# master-sim800.net
KiCad netlist of a schematic drawn in EAGLE
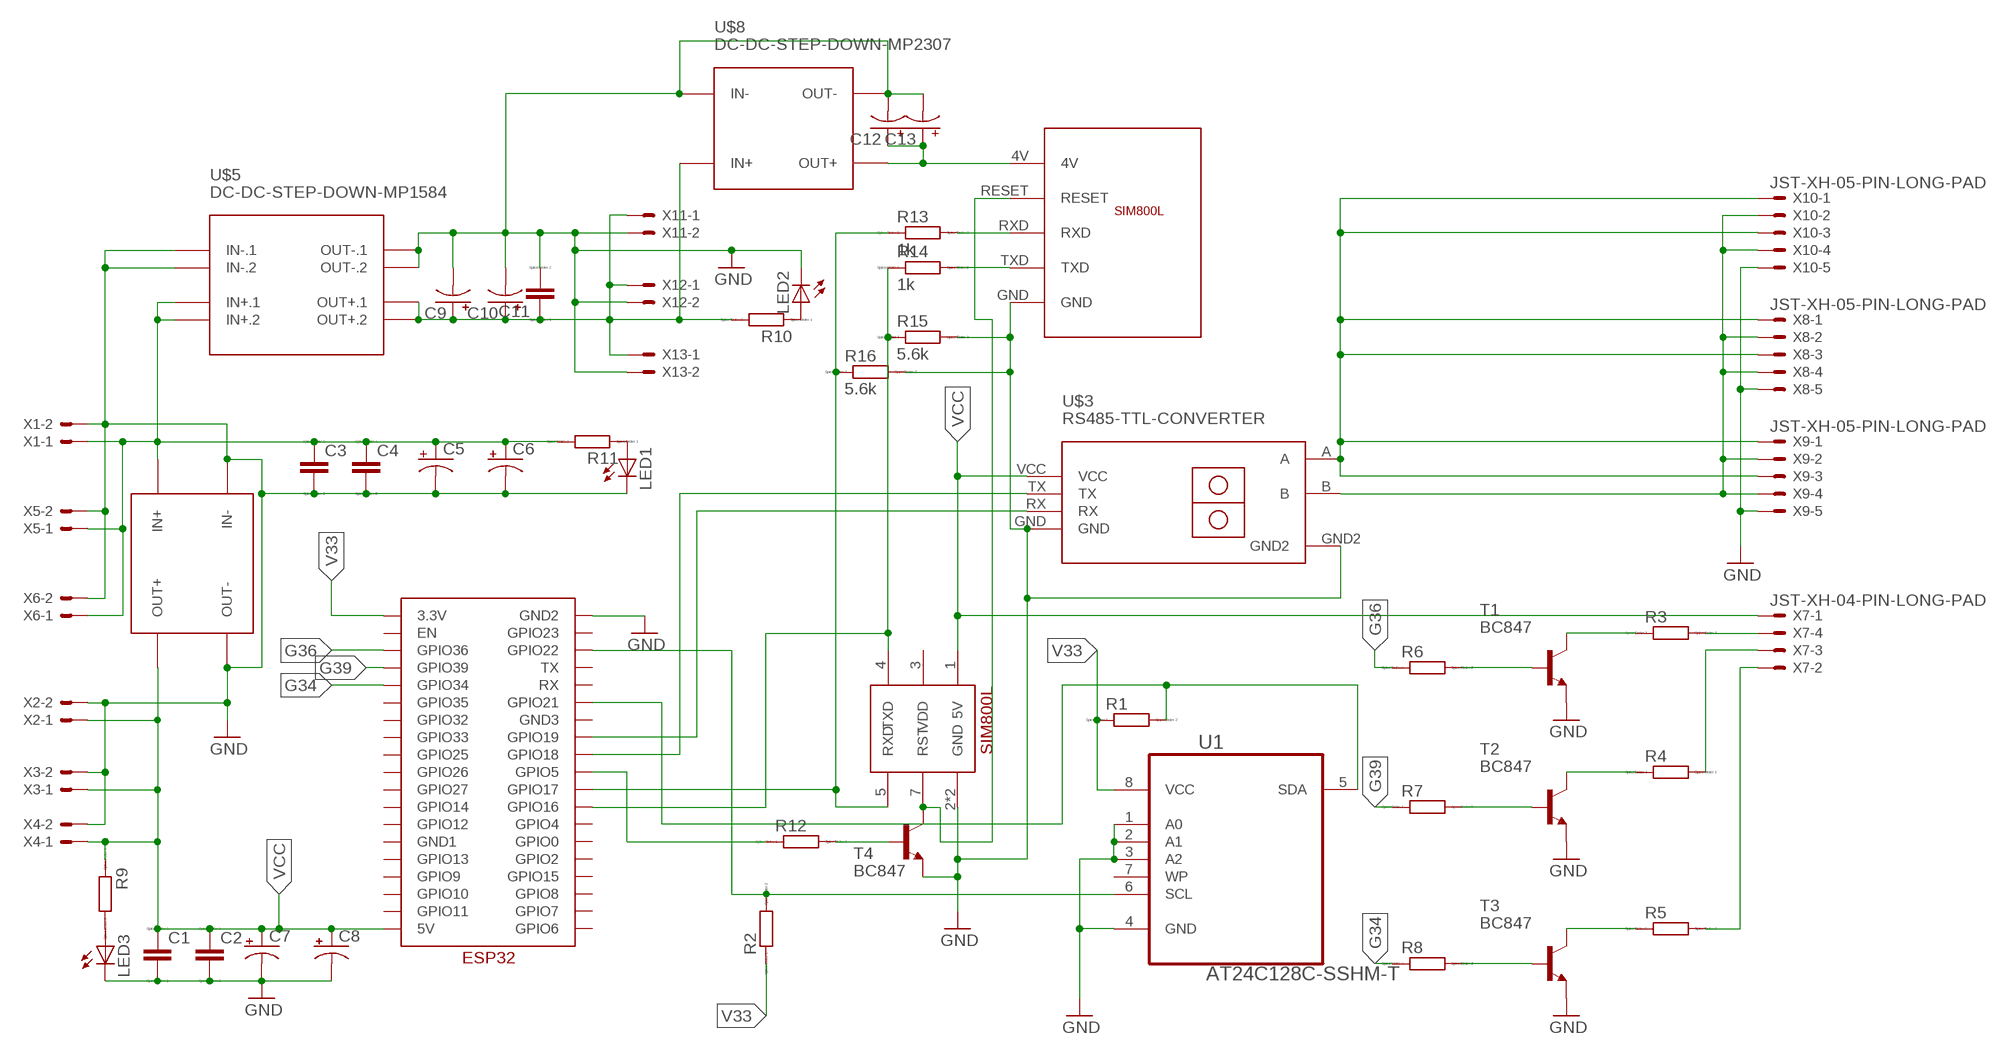
[diagram p0: schematic, sheet 1]

(export (version "E")
  (design (tool "Eeschema 10.0.6"))
  (components
    (comp (ref "C1") (value "C") (footprint "eagle-import:C0805") (libsource (lib "eagle-import") (part "C")))
    (comp (ref "C2") (value "C") (footprint "eagle-import:C0805") (libsource (lib "eagle-import") (part "C")))
    (comp (ref "C3") (value "C") (footprint "eagle-import:C0805") (libsource (lib "eagle-import") (part "C")))
    (comp (ref "C4") (value "C") (footprint "eagle-import:C0805") (libsource (lib "eagle-import") (part "C")))
    (comp (ref "C5")
      (value "CPOL-USE5-8.5")
      (footprint "eagle-import:E5-8,5")
      (libsource (lib "eagle-import") (part "CPOL-USE5-8.5"))
    )
    (comp (ref "C6")
      (value "CPOL-USE5-8.5")
      (footprint "eagle-import:E5-8,5")
      (libsource (lib "eagle-import") (part "CPOL-USE5-8.5"))
    )
    (comp (ref "C7")
      (value "CPOL-USE5-8.5")
      (footprint "eagle-import:E5-8,5")
      (libsource (lib "eagle-import") (part "CPOL-USE5-8.5"))
    )
    (comp (ref "C8")
      (value "CPOL-USE5-8.5")
      (footprint "eagle-import:E5-8,5")
      (libsource (lib "eagle-import") (part "CPOL-USE5-8.5"))
    )
    (comp (ref "C9")
      (value "CPOL-USE5-6")
      (footprint "eagle-import:E5-6")
      (libsource (lib "eagle-import") (part "CPOL-USE5-6"))
    )
    (comp (ref "C10")
      (value "CPOL-USE5-6")
      (footprint "eagle-import:E5-6")
      (libsource (lib "eagle-import") (part "CPOL-USE5-6"))
    )
    (comp (ref "C11")
      (value "C")
      (footprint "eagle-import:C0805")
      (libsource (lib "eagle-import") (part "C"))
    )
    (comp (ref "C12")
      (value "CPOL-USE5-8.5")
      (footprint "eagle-import:E5-8,5")
      (libsource (lib "eagle-import") (part "CPOL-USE5-8.5"))
    )
    (comp (ref "C13")
      (value "CPOL-USE5-8.5")
      (footprint "eagle-import:E5-8,5")
      (libsource (lib "eagle-import") (part "CPOL-USE5-8.5"))
    )
    (comp (ref "LED1")
      (value "LEDCHIPLED_1206")
      (footprint "eagle-import:CHIPLED_1206")
      (libsource (lib "eagle-import") (part "LEDCHIPLED_1206"))
    )
    (comp (ref "LED2")
      (value "LEDCHIPLED_1206")
      (footprint "eagle-import:CHIPLED_1206")
      (libsource (lib "eagle-import") (part "LEDCHIPLED_1206"))
    )
    (comp (ref "LED3")
      (value "LEDCHIPLED_1206")
      (footprint "eagle-import:CHIPLED_1206")
      (libsource (lib "eagle-import") (part "LEDCHIPLED_1206"))
    )
    (comp (ref "R1")
      (value "RR1206")
      (footprint "eagle-import:R1206")
      (libsource (lib "eagle-import") (part "RR1206"))
    )
    (comp (ref "R2")
      (value "RR1206")
      (footprint "eagle-import:R1206")
      (libsource (lib "eagle-import") (part "RR1206"))
    )
    (comp (ref "R3")
      (value "RR1206")
      (footprint "eagle-import:R1206")
      (libsource (lib "eagle-import") (part "RR1206"))
    )
    (comp (ref "R4")
      (value "RR1206")
      (footprint "eagle-import:R1206")
      (libsource (lib "eagle-import") (part "RR1206"))
    )
    (comp (ref "R5")
      (value "RR1206")
      (footprint "eagle-import:R1206")
      (libsource (lib "eagle-import") (part "RR1206"))
    )
    (comp (ref "R6")
      (value "RR1206")
      (footprint "eagle-import:R1206")
      (libsource (lib "eagle-import") (part "RR1206"))
    )
    (comp (ref "R7")
      (value "RR1206")
      (footprint "eagle-import:R1206")
      (libsource (lib "eagle-import") (part "RR1206"))
    )
    (comp (ref "R8")
      (value "RR1206")
      (footprint "eagle-import:R1206")
      (libsource (lib "eagle-import") (part "RR1206"))
    )
    (comp (ref "R9")
      (value "RR1206")
      (footprint "eagle-import:R1206")
      (libsource (lib "eagle-import") (part "RR1206"))
    )
    (comp (ref "R10")
      (value "RR1206")
      (footprint "eagle-import:R1206")
      (libsource (lib "eagle-import") (part "RR1206"))
    )
    (comp (ref "R11")
      (value "RR1206")
      (footprint "eagle-import:R1206")
      (libsource (lib "eagle-import") (part "RR1206"))
    )
    (comp (ref "R12")
      (value "RR1206")
      (footprint "eagle-import:R1206")
      (libsource (lib "eagle-import") (part "RR1206"))
    )
    (comp (ref "R13")
      (value "1k")
      (footprint "eagle-import:R1206")
      (libsource (lib "eagle-import") (part "RR1206"))
    )
    (comp (ref "R14")
      (value "1k")
      (footprint "eagle-import:R1206")
      (libsource (lib "eagle-import") (part "RR1206"))
    )
    (comp (ref "R15")
      (value "5.6k")
      (footprint "eagle-import:R1206")
      (libsource (lib "eagle-import") (part "RR1206"))
    )
    (comp (ref "R16")
      (value "5.6k")
      (footprint "eagle-import:R1206")
      (libsource (lib "eagle-import") (part "RR1206"))
    )
    (comp (ref "T1")
      (value "BC847")
      (footprint "eagle-import:SOT23")
      (libsource (lib "eagle-import") (part "BC847"))
    )
    (comp (ref "T2")
      (value "BC847")
      (footprint "eagle-import:SOT23")
      (libsource (lib "eagle-import") (part "BC847"))
    )
    (comp (ref "T3")
      (value "BC847")
      (footprint "eagle-import:SOT23")
      (libsource (lib "eagle-import") (part "BC847"))
    )
    (comp (ref "T4")
      (value "BC847")
      (footprint "eagle-import:SOT23")
      (libsource (lib "eagle-import") (part "BC847"))
    )
    (comp (ref "U$1")
      (value "ESP32")
      (footprint "eagle-import:ESP32")
      (libsource (lib "eagle-import") (part "ESP32"))
    )
    (comp (ref "U$2")
      (value "SIM800L")
      (footprint "eagle-import:SIP")
      (libsource (lib "eagle-import") (part "SIM800L"))
    )
    (comp (ref "U$3")
      (value "RS485-TTL-CONVERTER")
      (footprint "eagle-import:RS485-TTL-CONVERTER")
      (libsource (lib "eagle-import") (part "RS485-TTL-CONVERTER"))
    )
    (comp (ref "U$4")
      (value "DC-DC-STEP-DOWN-MP2307")
      (footprint "eagle-import:DC-DC-STEP-DOWN-MP2307")
      (libsource (lib "eagle-import") (part "DC-DC-STEP-DOWN-MP2307"))
    )
    (comp (ref "U$5")
      (value "DC-DC-STEP-DOWN-MP1584")
      (footprint "eagle-import:DC-DC-STEP-DOWN-MP1584")
      (libsource (lib "eagle-import") (part "DC-DC-STEP-DOWN-MP1584"))
    )
    (comp (ref "U$7")
      (value "SIM800L-V1")
      (footprint "eagle-import:SIM800L")
      (libsource (lib "eagle-import") (part "SIM800L-V1"))
    )
    (comp (ref "U$8")
      (value "DC-DC-STEP-DOWN-MP2307")
      (footprint "eagle-import:DC-DC-STEP-DOWN-MP2307")
      (libsource (lib "eagle-import") (part "DC-DC-STEP-DOWN-MP2307"))
    )
    (comp (ref "U1")
      (value "AT24C128C-SSHM-T")
      (footprint "eagle-import:SOIC127P600X175-8N")
      (fields (field (name "MF") "Microchip"))
      (libsource (lib "eagle-import") (part "AT24C128C-SSHM-T"))
    )
    (comp (ref "X1")
      (value "JST-XH-02-PIN-LONG-PAD")
      (footprint "eagle-import:JST-XH-02-PACKAGE-LONG-PAD")
      (libsource (lib "eagle-import") (part "JST-XH-02-PIN-LONG-PAD"))
    )
    (comp (ref "X2")
      (value "JST-XH-02-PIN-LONG-PAD")
      (footprint "eagle-import:JST-XH-02-PACKAGE-LONG-PAD")
      (libsource (lib "eagle-import") (part "JST-XH-02-PIN-LONG-PAD"))
    )
    (comp (ref "X3")
      (value "JST-XH-02-PIN-LONG-PAD")
      (footprint "eagle-import:JST-XH-02-PACKAGE-LONG-PAD")
      (libsource (lib "eagle-import") (part "JST-XH-02-PIN-LONG-PAD"))
    )
    (comp (ref "X4")
      (value "JST-XH-02-PIN-LONG-PAD")
      (footprint "eagle-import:JST-XH-02-PACKAGE-LONG-PAD")
      (libsource (lib "eagle-import") (part "JST-XH-02-PIN-LONG-PAD"))
    )
    (comp (ref "X5")
      (value "JST-XH-02-PIN-LONG-PAD")
      (footprint "eagle-import:JST-XH-02-PACKAGE-LONG-PAD")
      (libsource (lib "eagle-import") (part "JST-XH-02-PIN-LONG-PAD"))
    )
    (comp (ref "X6")
      (value "JST-XH-02-PIN-LONG-PAD")
      (footprint "eagle-import:JST-XH-02-PACKAGE-LONG-PAD")
      (libsource (lib "eagle-import") (part "JST-XH-02-PIN-LONG-PAD"))
    )
    (comp (ref "X7")
      (value "JST-XH-04-PIN-LONG-PAD")
      (footprint "eagle-import:JST-XH-04-PACKAGE-LONG-PAD")
      (libsource (lib "eagle-import") (part "JST-XH-04-PIN-LONG-PAD"))
    )
    (comp (ref "X8")
      (value "JST-XH-05-PIN-LONG-PAD")
      (footprint "eagle-import:JST-XH-05-PACKAGE-LONG-PAD")
      (libsource (lib "eagle-import") (part "JST-XH-05-PIN-LONG-PAD"))
    )
    (comp (ref "X9")
      (value "JST-XH-05-PIN-LONG-PAD")
      (footprint "eagle-import:JST-XH-05-PACKAGE-LONG-PAD")
      (libsource (lib "eagle-import") (part "JST-XH-05-PIN-LONG-PAD"))
    )
    (comp (ref "X10")
      (value "JST-XH-05-PIN-LONG-PAD")
      (footprint "eagle-import:JST-XH-05-PACKAGE-LONG-PAD")
      (libsource (lib "eagle-import") (part "JST-XH-05-PIN-LONG-PAD"))
    )
    (comp (ref "X11")
      (value "JST-XH-02-PIN-LONG-PAD")
      (footprint "eagle-import:JST-XH-02-PACKAGE-LONG-PAD")
      (libsource (lib "eagle-import") (part "JST-XH-02-PIN-LONG-PAD"))
    )
    (comp (ref "X12")
      (value "JST-XH-02-PIN-LONG-PAD")
      (footprint "eagle-import:JST-XH-02-PACKAGE-LONG-PAD")
      (libsource (lib "eagle-import") (part "JST-XH-02-PIN-LONG-PAD"))
    )
    (comp (ref "X13")
      (value "JST-XH-02-PIN-LONG-PAD")
      (footprint "eagle-import:JST-XH-02-PACKAGE-LONG-PAD")
      (libsource (lib "eagle-import") (part "JST-XH-02-PIN-LONG-PAD"))
    )
  )
  (nets
    (net (code "1") (name "G34") (class "Default")
      (node (ref "R8") (pin "1") (pinfunction "1_1") (pintype "passive"))
      (node (ref "U$1") (pin "GPIO34") (pinfunction "GPIO34_GPIO34") (pintype "bidirectional"))
    )
    (net (code "2") (name "G36") (class "Default")
      (node (ref "R6") (pin "1") (pinfunction "1_1") (pintype "passive"))
      (node (ref "U$1") (pin "GPIO36") (pinfunction "GPIO36_GPIO36") (pintype "bidirectional"))
    )
    (net (code "3") (name "G39") (class "Default")
      (node (ref "R7") (pin "1") (pinfunction "1_1") (pintype "passive"))
      (node (ref "U$1") (pin "GPIO39") (pinfunction "GPIO39_GPIO39") (pintype "bidirectional"))
    )
    (net (code "4") (name "GND") (class "Default")
      (node (ref "C1") (pin "2") (pinfunction "2_2") (pintype "passive"))
      (node (ref "C10") (pin "-") (pinfunction "-_-") (pintype "passive"))
      (node (ref "C11") (pin "2") (pinfunction "2_2") (pintype "passive"))
      (node (ref "C12") (pin "-") (pinfunction "-_-") (pintype "passive"))
      (node (ref "C13") (pin "-") (pinfunction "-_-") (pintype "passive"))
      (node (ref "C2") (pin "2") (pinfunction "2_2") (pintype "passive"))
      (node (ref "C3") (pin "2") (pinfunction "2_2") (pintype "passive"))
      (node (ref "C4") (pin "2") (pinfunction "2_2") (pintype "passive"))
      (node (ref "C5") (pin "-") (pinfunction "-_-") (pintype "passive"))
      (node (ref "C6") (pin "-") (pinfunction "-_-") (pintype "passive"))
      (node (ref "C7") (pin "-") (pinfunction "-_-") (pintype "passive"))
      (node (ref "C8") (pin "-") (pinfunction "-_-") (pintype "passive"))
      (node (ref "C9") (pin "-") (pinfunction "-_-") (pintype "passive"))
      (node (ref "LED1") (pin "C") (pinfunction "C_C") (pintype "passive"))
      (node (ref "LED2") (pin "C") (pinfunction "C_C") (pintype "passive"))
      (node (ref "LED3") (pin "C") (pinfunction "C_C") (pintype "passive"))
      (node (ref "R15") (pin "2") (pinfunction "2_2") (pintype "passive"))
      (node (ref "R16") (pin "2") (pinfunction "2_2") (pintype "passive"))
      (node (ref "T1") (pin "2") (pinfunction "E_2") (pintype "passive"))
      (node (ref "T2") (pin "2") (pinfunction "E_2") (pintype "passive"))
      (node (ref "T3") (pin "2") (pinfunction "E_2") (pintype "passive"))
      (node (ref "T4") (pin "2") (pinfunction "E_2") (pintype "passive"))
      (node (ref "U$1") (pin "GND2") (pinfunction "GND2_GND2") (pintype "bidirectional"))
      (node (ref "U$2") (pin "2") (pinfunction "GND_2") (pintype "bidirectional"))
      (node (ref "U$2") (pin "6") (pinfunction "GND_6") (pintype "bidirectional"))
      (node (ref "U$3") (pin "GND") (pinfunction "GND_GND") (pintype "passive"))
      (node (ref "U$3") (pin "GND2") (pinfunction "GND2_GND2") (pintype "power_in"))
      (node (ref "U$4") (pin "IN-") (pinfunction "IN-_IN-") (pintype "bidirectional"))
      (node (ref "U$4") (pin "OUT-") (pinfunction "OUT-_OUT-") (pintype "bidirectional"))
      (node (ref "U$5") (pin "IN-.1") (pinfunction "IN-.1_IN-.1") (pintype "bidirectional"))
      (node (ref "U$5") (pin "IN-.2") (pinfunction "IN-.2_IN-.2") (pintype "bidirectional"))
      (node (ref "U$5") (pin "OUT-.1") (pinfunction "OUT-.1_OUT-.1") (pintype "bidirectional"))
      (node (ref "U$5") (pin "OUT-.2") (pinfunction "OUT-.2_OUT-.2") (pintype "bidirectional"))
      (node (ref "U$7") (pin "GND") (pinfunction "GND_GND") (pintype "bidirectional"))
      (node (ref "U$8") (pin "IN-") (pinfunction "IN-_IN-") (pintype "bidirectional"))
      (node (ref "U$8") (pin "OUT-") (pinfunction "OUT-_OUT-") (pintype "bidirectional"))
      (node (ref "U1") (pin "1") (pinfunction "A0_1") (pintype "input"))
      (node (ref "U1") (pin "2") (pinfunction "A1_2") (pintype "input"))
      (node (ref "U1") (pin "3") (pinfunction "A2_3") (pintype "input"))
      (node (ref "U1") (pin "4") (pinfunction "GND_4") (pintype "passive"))
      (node (ref "X1") (pin "2") (pinfunction "S_2") (pintype "passive"))
      (node (ref "X10") (pin "5") (pinfunction "S_5") (pintype "passive"))
      (node (ref "X11") (pin "2") (pinfunction "S_2") (pintype "passive"))
      (node (ref "X12") (pin "2") (pinfunction "S_2") (pintype "passive"))
      (node (ref "X13") (pin "2") (pinfunction "S_2") (pintype "passive"))
      (node (ref "X2") (pin "2") (pinfunction "S_2") (pintype "passive"))
      (node (ref "X3") (pin "2") (pinfunction "S_2") (pintype "passive"))
      (node (ref "X4") (pin "2") (pinfunction "S_2") (pintype "passive"))
      (node (ref "X5") (pin "2") (pinfunction "S_2") (pintype "passive"))
      (node (ref "X6") (pin "2") (pinfunction "S_2") (pintype "passive"))
      (node (ref "X8") (pin "5") (pinfunction "S_5") (pintype "passive"))
      (node (ref "X9") (pin "5") (pinfunction "S_5") (pintype "passive"))
    )
    (net (code "5") (name "Net-(C12-Pad+)") (class "Default")
      (node (ref "C12") (pin "+") (pinfunction "+_+") (pintype "passive"))
      (node (ref "C13") (pin "+") (pinfunction "+_+") (pintype "passive"))
      (node (ref "U$7") (pin "4V") (pinfunction "4V_4V") (pintype "bidirectional"))
      (node (ref "U$8") (pin "OUT+") (pinfunction "OUT+_OUT+") (pintype "bidirectional"))
    )
    (net (code "6") (name "Net-(LED1-PadA)") (class "Default")
      (node (ref "LED1") (pin "A") (pinfunction "A_A") (pintype "passive"))
      (node (ref "R11") (pin "1") (pinfunction "1_1") (pintype "passive"))
    )
    (net (code "7") (name "Net-(LED2-PadA)") (class "Default")
      (node (ref "LED2") (pin "A") (pinfunction "A_A") (pintype "passive"))
      (node (ref "R10") (pin "1") (pinfunction "1_1") (pintype "passive"))
    )
    (net (code "8") (name "Net-(LED3-PadA)") (class "Default")
      (node (ref "LED3") (pin "A") (pinfunction "A_A") (pintype "passive"))
      (node (ref "R9") (pin "2") (pinfunction "2_2") (pintype "passive"))
    )
    (net (code "9") (name "Net-(R12-Pad1)") (class "Default")
      (node (ref "R12") (pin "1") (pinfunction "1_1") (pintype "passive"))
      (node (ref "U$1") (pin "GPIO5") (pinfunction "GPIO5_GPIO5") (pintype "bidirectional"))
    )
    (net (code "10") (name "Net-(R13-Pad2)") (class "Default")
      (node (ref "R13") (pin "2") (pinfunction "2_2") (pintype "passive"))
      (node (ref "U$7") (pin "RXD") (pinfunction "RXD_RXD") (pintype "bidirectional"))
    )
    (net (code "11") (name "Net-(R14-Pad2)") (class "Default")
      (node (ref "R14") (pin "2") (pinfunction "2_2") (pintype "passive"))
      (node (ref "U$7") (pin "TXD") (pinfunction "TXD_TXD") (pintype "bidirectional"))
    )
    (net (code "12") (name "Net-(T1-B)") (class "Default")
      (node (ref "R6") (pin "2") (pinfunction "2_2") (pintype "passive"))
      (node (ref "T1") (pin "1") (pinfunction "B_1") (pintype "passive"))
    )
    (net (code "13") (name "Net-(T1-C)") (class "Default")
      (node (ref "R3") (pin "1") (pinfunction "1_1") (pintype "passive"))
      (node (ref "T1") (pin "3") (pinfunction "C_3") (pintype "passive"))
    )
    (net (code "14") (name "Net-(T2-B)") (class "Default")
      (node (ref "R7") (pin "2") (pinfunction "2_2") (pintype "passive"))
      (node (ref "T2") (pin "1") (pinfunction "B_1") (pintype "passive"))
    )
    (net (code "15") (name "Net-(T2-C)") (class "Default")
      (node (ref "R4") (pin "1") (pinfunction "1_1") (pintype "passive"))
      (node (ref "T2") (pin "3") (pinfunction "C_3") (pintype "passive"))
    )
    (net (code "16") (name "Net-(T3-B)") (class "Default")
      (node (ref "R8") (pin "2") (pinfunction "2_2") (pintype "passive"))
      (node (ref "T3") (pin "1") (pinfunction "B_1") (pintype "passive"))
    )
    (net (code "17") (name "Net-(T3-C)") (class "Default")
      (node (ref "R5") (pin "1") (pinfunction "1_1") (pintype "passive"))
      (node (ref "T3") (pin "3") (pinfunction "C_3") (pintype "passive"))
    )
    (net (code "18") (name "Net-(T4-B)") (class "Default")
      (node (ref "R12") (pin "2") (pinfunction "2_2") (pintype "passive"))
      (node (ref "T4") (pin "1") (pinfunction "B_1") (pintype "passive"))
    )
    (net (code "19") (name "Net-(T4-C)") (class "Default")
      (node (ref "T4") (pin "3") (pinfunction "C_3") (pintype "passive"))
      (node (ref "U$2") (pin "7") (pinfunction "RST_7") (pintype "bidirectional"))
      (node (ref "U$7") (pin "RESET") (pinfunction "RESET_RESET") (pintype "bidirectional"))
    )
    (net (code "20") (name "Net-(U$1-PadGPIO18)") (class "Default")
      (node (ref "U$1") (pin "GPIO18") (pinfunction "GPIO18_GPIO18") (pintype "bidirectional"))
      (node (ref "U$3") (pin "TX") (pinfunction "TX_TX") (pintype "passive"))
    )
    (net (code "21") (name "Net-(U$1-PadGPIO19)") (class "Default")
      (node (ref "U$1") (pin "GPIO19") (pinfunction "GPIO19_GPIO19") (pintype "bidirectional"))
      (node (ref "U$3") (pin "RX") (pinfunction "RX_RX") (pintype "passive"))
    )
    (net (code "22") (name "Net-(U$2-RXD)") (class "Default")
      (node (ref "R13") (pin "1") (pinfunction "1_1") (pintype "passive"))
      (node (ref "R16") (pin "1") (pinfunction "1_1") (pintype "passive"))
      (node (ref "U$1") (pin "GPIO17") (pinfunction "GPIO17_GPIO17") (pintype "bidirectional"))
      (node (ref "U$2") (pin "5") (pinfunction "RXD_5") (pintype "bidirectional"))
    )
    (net (code "23") (name "Net-(U$2-TXD)") (class "Default")
      (node (ref "R14") (pin "1") (pinfunction "1_1") (pintype "passive"))
      (node (ref "R15") (pin "1") (pinfunction "1_1") (pintype "passive"))
      (node (ref "U$1") (pin "GPIO16") (pinfunction "GPIO16_GPIO16") (pintype "bidirectional"))
      (node (ref "U$2") (pin "4") (pinfunction "TXD_4") (pintype "bidirectional"))
    )
    (net (code "24") (name "Net-(U1-SCL)") (class "Default")
      (node (ref "R2") (pin "2") (pinfunction "2_2") (pintype "passive"))
      (node (ref "U$1") (pin "GPIO22") (pinfunction "GPIO22_GPIO22") (pintype "bidirectional"))
      (node (ref "U1") (pin "6") (pinfunction "SCL_6") (pintype "input"))
    )
    (net (code "25") (name "Net-(U1-SDA)") (class "Default")
      (node (ref "R1") (pin "2") (pinfunction "2_2") (pintype "passive"))
      (node (ref "U$1") (pin "GPIO21") (pinfunction "GPIO21_GPIO21") (pintype "bidirectional"))
      (node (ref "U1") (pin "5") (pinfunction "SDA_5") (pintype "bidirectional"))
    )
    (net (code "26") (name "Net-(X1A-S)") (class "Default")
      (node (ref "C3") (pin "1") (pinfunction "1_1") (pintype "passive"))
      (node (ref "C4") (pin "1") (pinfunction "1_1") (pintype "passive"))
      (node (ref "C5") (pin "+") (pinfunction "+_+") (pintype "passive"))
      (node (ref "C6") (pin "+") (pinfunction "+_+") (pintype "passive"))
      (node (ref "R11") (pin "2") (pinfunction "2_2") (pintype "passive"))
      (node (ref "U$4") (pin "IN+") (pinfunction "IN+_IN+") (pintype "bidirectional"))
      (node (ref "U$5") (pin "IN+.1") (pinfunction "IN+.1_IN+.1") (pintype "bidirectional"))
      (node (ref "U$5") (pin "IN+.2") (pinfunction "IN+.2_IN+.2") (pintype "bidirectional"))
      (node (ref "X1") (pin "1") (pinfunction "S_1") (pintype "passive"))
      (node (ref "X5") (pin "1") (pinfunction "S_1") (pintype "passive"))
      (node (ref "X6") (pin "1") (pinfunction "S_1") (pintype "passive"))
    )
    (net (code "27") (name "Net-(X7B-S)") (class "Default")
      (node (ref "R5") (pin "2") (pinfunction "2_2") (pintype "passive"))
      (node (ref "X7") (pin "2") (pinfunction "S_2") (pintype "passive"))
    )
    (net (code "28") (name "Net-(X7C-S)") (class "Default")
      (node (ref "R4") (pin "2") (pinfunction "2_2") (pintype "passive"))
      (node (ref "X7") (pin "3") (pinfunction "S_3") (pintype "passive"))
    )
    (net (code "29") (name "Net-(X7D-S)") (class "Default")
      (node (ref "R3") (pin "2") (pinfunction "2_2") (pintype "passive"))
      (node (ref "X7") (pin "4") (pinfunction "S_4") (pintype "passive"))
    )
    (net (code "30") (name "Net-(X10A-S)") (class "Default")
      (node (ref "U$3") (pin "A") (pinfunction "A_A") (pintype "passive"))
      (node (ref "X10") (pin "1") (pinfunction "S_1") (pintype "passive"))
      (node (ref "X10") (pin "3") (pinfunction "S_3") (pintype "passive"))
      (node (ref "X8") (pin "1") (pinfunction "S_1") (pintype "passive"))
      (node (ref "X8") (pin "3") (pinfunction "S_3") (pintype "passive"))
      (node (ref "X9") (pin "1") (pinfunction "S_1") (pintype "passive"))
      (node (ref "X9") (pin "3") (pinfunction "S_3") (pintype "passive"))
    )
    (net (code "31") (name "Net-(X10B-S)") (class "Default")
      (node (ref "U$3") (pin "B") (pinfunction "B_B") (pintype "passive"))
      (node (ref "X10") (pin "2") (pinfunction "S_2") (pintype "passive"))
      (node (ref "X10") (pin "4") (pinfunction "S_4") (pintype "passive"))
      (node (ref "X8") (pin "2") (pinfunction "S_2") (pintype "passive"))
      (node (ref "X8") (pin "4") (pinfunction "S_4") (pintype "passive"))
      (node (ref "X9") (pin "2") (pinfunction "S_2") (pintype "passive"))
      (node (ref "X9") (pin "4") (pinfunction "S_4") (pintype "passive"))
    )
    (net (code "32") (name "Net-(X11A-S)") (class "Default")
      (node (ref "C10") (pin "+") (pinfunction "+_+") (pintype "passive"))
      (node (ref "C11") (pin "1") (pinfunction "1_1") (pintype "passive"))
      (node (ref "C9") (pin "+") (pinfunction "+_+") (pintype "passive"))
      (node (ref "R10") (pin "2") (pinfunction "2_2") (pintype "passive"))
      (node (ref "U$5") (pin "OUT+.1") (pinfunction "OUT+.1_OUT+.1") (pintype "bidirectional"))
      (node (ref "U$5") (pin "OUT+.2") (pinfunction "OUT+.2_OUT+.2") (pintype "bidirectional"))
      (node (ref "U$8") (pin "IN+") (pinfunction "IN+_IN+") (pintype "bidirectional"))
      (node (ref "X11") (pin "1") (pinfunction "S_1") (pintype "passive"))
      (node (ref "X12") (pin "1") (pinfunction "S_1") (pintype "passive"))
      (node (ref "X13") (pin "1") (pinfunction "S_1") (pintype "passive"))
    )
    (net (code "33") (name "V33") (class "Default")
      (node (ref "R1") (pin "1") (pinfunction "1_1") (pintype "passive"))
      (node (ref "R2") (pin "1") (pinfunction "1_1") (pintype "passive"))
      (node (ref "U$1") (pin "3.3V") (pinfunction "3.3V_3.3V") (pintype "bidirectional"))
      (node (ref "U1") (pin "8") (pinfunction "VCC_8") (pintype "power_in"))
    )
    (net (code "34") (name "VCC") (class "Default")
      (node (ref "C1") (pin "1") (pinfunction "1_1") (pintype "passive"))
      (node (ref "C2") (pin "1") (pinfunction "1_1") (pintype "passive"))
      (node (ref "C7") (pin "+") (pinfunction "+_+") (pintype "passive"))
      (node (ref "C8") (pin "+") (pinfunction "+_+") (pintype "passive"))
      (node (ref "R9") (pin "1") (pinfunction "1_1") (pintype "passive"))
      (node (ref "U$1") (pin "5V") (pinfunction "5V_5V") (pintype "bidirectional"))
      (node (ref "U$2") (pin "1") (pinfunction "5V_1") (pintype "bidirectional"))
      (node (ref "U$3") (pin "VCC") (pinfunction "VCC_VCC") (pintype "passive"))
      (node (ref "U$4") (pin "OUT+") (pinfunction "OUT+_OUT+") (pintype "bidirectional"))
      (node (ref "X2") (pin "1") (pinfunction "S_1") (pintype "passive"))
      (node (ref "X3") (pin "1") (pinfunction "S_1") (pintype "passive"))
      (node (ref "X4") (pin "1") (pinfunction "S_1") (pintype "passive"))
      (node (ref "X7") (pin "1") (pinfunction "S_1") (pintype "passive"))
    )
    (net (code "35") (name "unconnected-(U$1-PadEN)") (class "Default")
      (node (ref "U$1") (pin "EN") (pinfunction "EN_EN") (pintype "bidirectional"))
    )
    (net (code "36") (name "unconnected-(U$1-PadGND1)") (class "Default")
      (node (ref "U$1") (pin "GND1") (pinfunction "GND1_GND1") (pintype "bidirectional"))
    )
    (net (code "37") (name "unconnected-(U$1-PadGND3)") (class "Default")
      (node (ref "U$1") (pin "GND3") (pinfunction "GND3_GND3") (pintype "bidirectional"))
    )
    (net (code "38") (name "unconnected-(U$1-PadGPIO0)") (class "Default")
      (node (ref "U$1") (pin "GPIO0") (pinfunction "GPIO0_GPIO0") (pintype "bidirectional"))
    )
    (net (code "39") (name "unconnected-(U$1-PadGPIO2)") (class "Default")
      (node (ref "U$1") (pin "GPIO2") (pinfunction "GPIO2_GPIO2") (pintype "bidirectional"))
    )
    (net (code "40") (name "unconnected-(U$1-PadGPIO4)") (class "Default")
      (node (ref "U$1") (pin "GPIO4") (pinfunction "GPIO4_GPIO4") (pintype "bidirectional"))
    )
    (net (code "41") (name "unconnected-(U$1-PadGPIO6)") (class "Default")
      (node (ref "U$1") (pin "GPIO6") (pinfunction "GPIO6_GPIO6") (pintype "bidirectional"))
    )
    (net (code "42") (name "unconnected-(U$1-PadGPIO7)") (class "Default")
      (node (ref "U$1") (pin "GPIO7") (pinfunction "GPIO7_GPIO7") (pintype "bidirectional"))
    )
    (net (code "43") (name "unconnected-(U$1-PadGPIO8)") (class "Default")
      (node (ref "U$1") (pin "GPIO8") (pinfunction "GPIO8_GPIO8") (pintype "bidirectional"))
    )
    (net (code "44") (name "unconnected-(U$1-PadGPIO9)") (class "Default")
      (node (ref "U$1") (pin "GPIO9") (pinfunction "GPIO9_GPIO9") (pintype "bidirectional"))
    )
    (net (code "45") (name "unconnected-(U$1-PadGPIO10)") (class "Default")
      (node (ref "U$1") (pin "GPIO10") (pinfunction "GPIO10_GPIO10") (pintype "bidirectional"))
    )
    (net (code "46") (name "unconnected-(U$1-PadGPIO11)") (class "Default")
      (node (ref "U$1") (pin "GPIO11") (pinfunction "GPIO11_GPIO11") (pintype "bidirectional"))
    )
    (net (code "47") (name "unconnected-(U$1-PadGPIO12)") (class "Default")
      (node (ref "U$1") (pin "GPIO12") (pinfunction "GPIO12_GPIO12") (pintype "bidirectional"))
    )
    (net (code "48") (name "unconnected-(U$1-PadGPIO13)") (class "Default")
      (node (ref "U$1") (pin "GPIO13") (pinfunction "GPIO13_GPIO13") (pintype "bidirectional"))
    )
    (net (code "49") (name "unconnected-(U$1-PadGPIO14)") (class "Default")
      (node (ref "U$1") (pin "GPIO14") (pinfunction "GPIO14_GPIO14") (pintype "bidirectional"))
    )
    (net (code "50") (name "unconnected-(U$1-PadGPIO15)") (class "Default")
      (node (ref "U$1") (pin "GPIO15") (pinfunction "GPIO15_GPIO15") (pintype "bidirectional"))
    )
    (net (code "51") (name "unconnected-(U$1-PadGPIO23)") (class "Default")
      (node (ref "U$1") (pin "GPIO23") (pinfunction "GPIO23_GPIO23") (pintype "bidirectional"))
    )
    (net (code "52") (name "unconnected-(U$1-PadGPIO25)") (class "Default")
      (node (ref "U$1") (pin "GPIO25") (pinfunction "GPIO25_GPIO25") (pintype "bidirectional"))
    )
    (net (code "53") (name "unconnected-(U$1-PadGPIO26)") (class "Default")
      (node (ref "U$1") (pin "GPIO26") (pinfunction "GPIO26_GPIO26") (pintype "bidirectional"))
    )
    (net (code "54") (name "unconnected-(U$1-PadGPIO27)") (class "Default")
      (node (ref "U$1") (pin "GPIO27") (pinfunction "GPIO27_GPIO27") (pintype "bidirectional"))
    )
    (net (code "55") (name "unconnected-(U$1-PadGPIO32)") (class "Default")
      (node (ref "U$1") (pin "GPIO32") (pinfunction "GPIO32_GPIO32") (pintype "bidirectional"))
    )
    (net (code "56") (name "unconnected-(U$1-PadGPIO33)") (class "Default")
      (node (ref "U$1") (pin "GPIO33") (pinfunction "GPIO33_GPIO33") (pintype "bidirectional"))
    )
    (net (code "57") (name "unconnected-(U$1-PadGPIO35)") (class "Default")
      (node (ref "U$1") (pin "GPIO35") (pinfunction "GPIO35_GPIO35") (pintype "bidirectional"))
    )
    (net (code "58") (name "unconnected-(U$1-PadRX)") (class "Default")
      (node (ref "U$1") (pin "RX") (pinfunction "RX_RX") (pintype "bidirectional"))
    )
    (net (code "59") (name "unconnected-(U$1-PadTX)") (class "Default")
      (node (ref "U$1") (pin "TX") (pinfunction "TX_TX") (pintype "bidirectional"))
    )
    (net (code "60") (name "unconnected-(U$2-VDD-Pad3)") (class "Default")
      (node (ref "U$2") (pin "3") (pinfunction "VDD_3") (pintype "bidirectional"))
    )
    (net (code "61") (name "unconnected-(U1-WP-Pad7)") (class "Default")
      (node (ref "U1") (pin "7") (pinfunction "WP_7") (pintype "input"))
    )
  )
)
